# LCD.net
KiCad netlist of a schematic drawn in Altium Designer
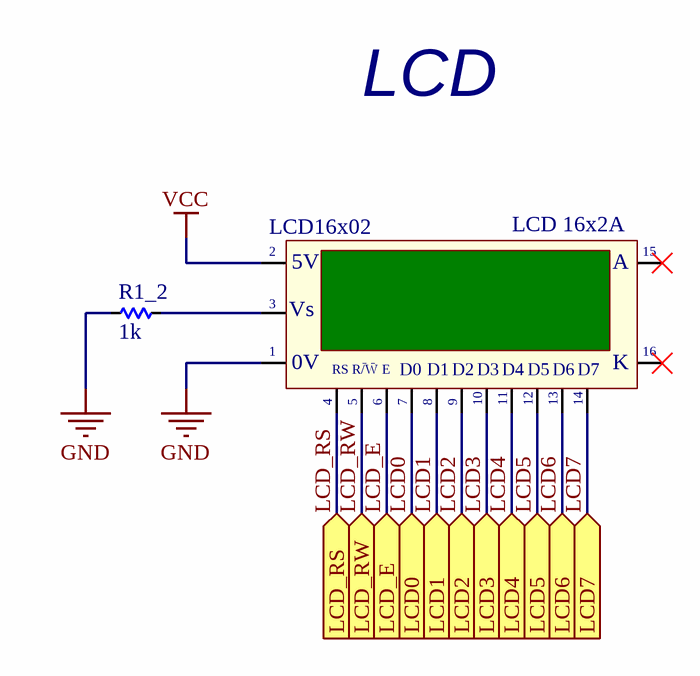
[diagram p0: LCD.SchDoc]

(export (version "E")
  (design (tool "Eeschema 10.0.6"))
  (components
    (comp (ref "LCD16x02")
      (value "LCD 16x2A")
      (footprint "LCD16X2")
      (description "LCD dipslay 16 char, 2 line")
      (libsource (lib "Altium Library") (part "LCD16x2A"))
    )
    (comp (ref "R1_2")
      (value "1k")
      (footprint "RES-SMD-0805")
      (description "Resistor")
      (fields
        (field (name "MANUFACTURER") "Generic Components")
        (field (name "PUBLISHER") "Altium Hobart Technology Centre")
      )
      (libsource (lib "Altium Library") (part "Res-SMD"))
    )
  )
  (nets
    (net (code "1") (name "/LCD0") (class "Default")
      (node (ref "LCD16x02") (pin "7") (pinfunction "D0_7") (pintype "passive"))
    )
    (net (code "2") (name "/LCD1") (class "Default")
      (node (ref "LCD16x02") (pin "8") (pinfunction "D1_8") (pintype "passive"))
    )
    (net (code "3") (name "/LCD2") (class "Default")
      (node (ref "LCD16x02") (pin "9") (pinfunction "D2_9") (pintype "passive"))
    )
    (net (code "4") (name "/LCD3") (class "Default")
      (node (ref "LCD16x02") (pin "10") (pinfunction "D3_10") (pintype "passive"))
    )
    (net (code "5") (name "/LCD4") (class "Default")
      (node (ref "LCD16x02") (pin "11") (pinfunction "D4_11") (pintype "passive"))
    )
    (net (code "6") (name "/LCD5") (class "Default")
      (node (ref "LCD16x02") (pin "12") (pinfunction "D5_12") (pintype "passive"))
    )
    (net (code "7") (name "/LCD6") (class "Default")
      (node (ref "LCD16x02") (pin "13") (pinfunction "D6_13") (pintype "passive"))
    )
    (net (code "8") (name "/LCD7") (class "Default")
      (node (ref "LCD16x02") (pin "14") (pinfunction "D7_14") (pintype "passive"))
    )
    (net (code "9") (name "/LCD_E") (class "Default")
      (node (ref "LCD16x02") (pin "6") (pinfunction "~{EN}_6") (pintype "passive"))
    )
    (net (code "10") (name "/LCD_RS") (class "Default")
      (node (ref "LCD16x02") (pin "4") (pinfunction "RS_4") (pintype "passive"))
    )
    (net (code "11") (name "/LCD_RW") (class "Default")
      (node (ref "LCD16x02") (pin "5") (pinfunction "R/~{W}_5") (pintype "passive"))
    )
    (net (code "12") (name "GND") (class "Default")
      (node (ref "LCD16x02") (pin "1") (pinfunction "GND_1") (pintype "passive"))
      (node (ref "R1_2") (pin "2") (pinfunction "2_2") (pintype "passive"))
    )
    (net (code "13") (name "Net-(LCD16x02-VEE)") (class "Default")
      (node (ref "LCD16x02") (pin "3") (pinfunction "VEE_3") (pintype "passive"))
      (node (ref "R1_2") (pin "1") (pinfunction "1_1") (pintype "passive"))
    )
    (net (code "14") (name "VCC") (class "Default")
      (node (ref "LCD16x02") (pin "2") (pinfunction "VDD_2") (pintype "passive"))
    )
    (net (code "15") (name "unconnected-(LCD16x02-A-Pad15)") (class "Default")
      (node (ref "LCD16x02") (pin "15") (pinfunction "A_15") (pintype "passive+no_connect"))
    )
    (net (code "16") (name "unconnected-(LCD16x02-K-Pad16)") (class "Default")
      (node (ref "LCD16x02") (pin "16") (pinfunction "K_16") (pintype "passive+no_connect"))
    )
  )
)
